# design.net
KiCad netlist of a schematic drawn in Altium Designer
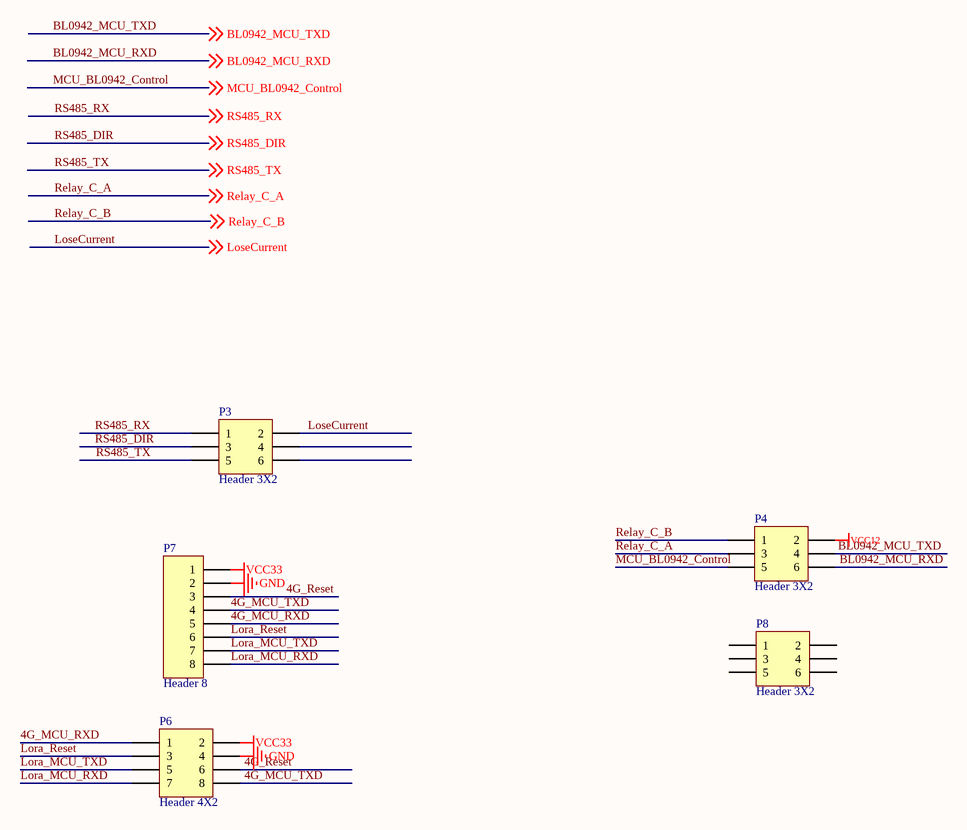
[diagram p0: 连接.SchDoc]

(export (version "E")
  (design (tool "Eeschema 10.0.6"))
  (components
    (comp (ref "P3")
      (value "Header 3X2")
      (footprint "CONN-SMD_5BME8-08872-203-W0")
      (description "Header, 3-Pin, Dual row")
      (fields (field (name "PUBLISHER") "Altium Limited"))
      (libsource (lib "Miscellaneous Connectors") (part "Header 3X2"))
    )
    (comp (ref "P4")
      (value "Header 3X2")
      (footprint "CONN-SMD_5BME8-08872-203-W0")
      (description "Header, 3-Pin, Dual row")
      (fields (field (name "PUBLISHER") "Altium Limited"))
      (libsource (lib "Miscellaneous Connectors") (part "Header 3X2"))
    )
    (comp (ref "P6")
      (value "Header 4X2")
      (footprint "CONN-SMD_5BME8-08872-204-W0")
      (description "Header, 4-Pin, Dual row")
      (fields (field (name "PUBLISHER") "Altium Limited"))
      (libsource (lib "Miscellaneous Connectors") (part "Header 4X2"))
    )
    (comp (ref "P7")
      (value "Header 8")
      (footprint "HDR1X8")
      (description "Header, 8-Pin")
      (fields (field (name "PUBLISHER") "Altium Limited"))
      (libsource (lib "Miscellaneous Connectors") (part "Header 8"))
    )
    (comp (ref "P8")
      (value "Header 3X2")
      (footprint "CONN-SMD_5BME8-08872-203-W0")
      (description "Header, 3-Pin, Dual row")
      (fields (field (name "PUBLISHER") "Altium Limited"))
      (libsource (lib "Miscellaneous Connectors") (part "Header 3X2"))
    )
  )
  (nets
    (net (code "1") (name "/4G_MCU_RXD") (class "Default")
      (node (ref "P6") (pin "1") (pinfunction "1_1") (pintype "passive"))
      (node (ref "P7") (pin "5") (pinfunction "5_5") (pintype "passive"))
    )
    (net (code "2") (name "/4G_MCU_TXD") (class "Default")
      (node (ref "P6") (pin "8") (pinfunction "8_8") (pintype "passive"))
      (node (ref "P7") (pin "4") (pinfunction "4_4") (pintype "passive"))
    )
    (net (code "3") (name "/4G_Reset") (class "Default")
      (node (ref "P6") (pin "6") (pinfunction "6_6") (pintype "passive"))
      (node (ref "P7") (pin "3") (pinfunction "3_3") (pintype "passive"))
    )
    (net (code "4") (name "/Lora_MCU_RXD") (class "Default")
      (node (ref "P6") (pin "7") (pinfunction "7_7") (pintype "passive"))
      (node (ref "P7") (pin "8") (pinfunction "8_8") (pintype "passive"))
    )
    (net (code "5") (name "/Lora_MCU_TXD") (class "Default")
      (node (ref "P6") (pin "5") (pinfunction "5_5") (pintype "passive"))
      (node (ref "P7") (pin "7") (pinfunction "7_7") (pintype "passive"))
    )
    (net (code "6") (name "/Lora_Reset") (class "Default")
      (node (ref "P6") (pin "3") (pinfunction "3_3") (pintype "passive"))
      (node (ref "P7") (pin "6") (pinfunction "6_6") (pintype "passive"))
    )
    (net (code "7") (name "BL0942_MCU_RXD") (class "Default")
      (node (ref "P4") (pin "6") (pinfunction "6_6") (pintype "passive"))
    )
    (net (code "8") (name "BL0942_MCU_TXD") (class "Default")
      (node (ref "P4") (pin "4") (pinfunction "4_4") (pintype "passive"))
    )
    (net (code "9") (name "GND") (class "Default")
      (node (ref "P6") (pin "4") (pinfunction "4_4") (pintype "passive"))
      (node (ref "P7") (pin "2") (pinfunction "2_2") (pintype "passive"))
    )
    (net (code "10") (name "LoseCurrent") (class "Default")
      (node (ref "P3") (pin "2") (pinfunction "2_2") (pintype "passive"))
    )
    (net (code "11") (name "MCU_BL0942_Control") (class "Default")
      (node (ref "P4") (pin "5") (pinfunction "5_5") (pintype "passive"))
    )
    (net (code "12") (name "RS485_DIR") (class "Default")
      (node (ref "P3") (pin "3") (pinfunction "3_3") (pintype "passive"))
    )
    (net (code "13") (name "RS485_RX") (class "Default")
      (node (ref "P3") (pin "1") (pinfunction "1_1") (pintype "passive"))
    )
    (net (code "14") (name "RS485_TX") (class "Default")
      (node (ref "P3") (pin "5") (pinfunction "5_5") (pintype "passive"))
    )
    (net (code "15") (name "Relay_C_A") (class "Default")
      (node (ref "P4") (pin "3") (pinfunction "3_3") (pintype "passive"))
    )
    (net (code "16") (name "Relay_C_B") (class "Default")
      (node (ref "P4") (pin "1") (pinfunction "1_1") (pintype "passive"))
    )
    (net (code "17") (name "VCC12") (class "Default")
      (node (ref "P4") (pin "2") (pinfunction "2_2") (pintype "passive"))
    )
    (net (code "18") (name "VCC33") (class "Default")
      (node (ref "P6") (pin "2") (pinfunction "2_2") (pintype "passive"))
      (node (ref "P7") (pin "1") (pinfunction "1_1") (pintype "passive"))
    )
    (net (code "19") (name "unconnected-(P3-Pad4)") (class "Default")
      (node (ref "P3") (pin "4") (pinfunction "4_4") (pintype "passive"))
    )
    (net (code "20") (name "unconnected-(P3-Pad6)") (class "Default")
      (node (ref "P3") (pin "6") (pinfunction "6_6") (pintype "passive"))
    )
    (net (code "21") (name "unconnected-(P8-Pad1)") (class "Default")
      (node (ref "P8") (pin "1") (pinfunction "1_1") (pintype "passive"))
    )
    (net (code "22") (name "unconnected-(P8-Pad2)") (class "Default")
      (node (ref "P8") (pin "2") (pinfunction "2_2") (pintype "passive"))
    )
    (net (code "23") (name "unconnected-(P8-Pad3)") (class "Default")
      (node (ref "P8") (pin "3") (pinfunction "3_3") (pintype "passive"))
    )
    (net (code "24") (name "unconnected-(P8-Pad4)") (class "Default")
      (node (ref "P8") (pin "4") (pinfunction "4_4") (pintype "passive"))
    )
    (net (code "25") (name "unconnected-(P8-Pad5)") (class "Default")
      (node (ref "P8") (pin "5") (pinfunction "5_5") (pintype "passive"))
    )
    (net (code "26") (name "unconnected-(P8-Pad6)") (class "Default")
      (node (ref "P8") (pin "6") (pinfunction "6_6") (pintype "passive"))
    )
  )
)
